# esp8266_minsys.net
KiCad netlist of a schematic drawn in EAGLE
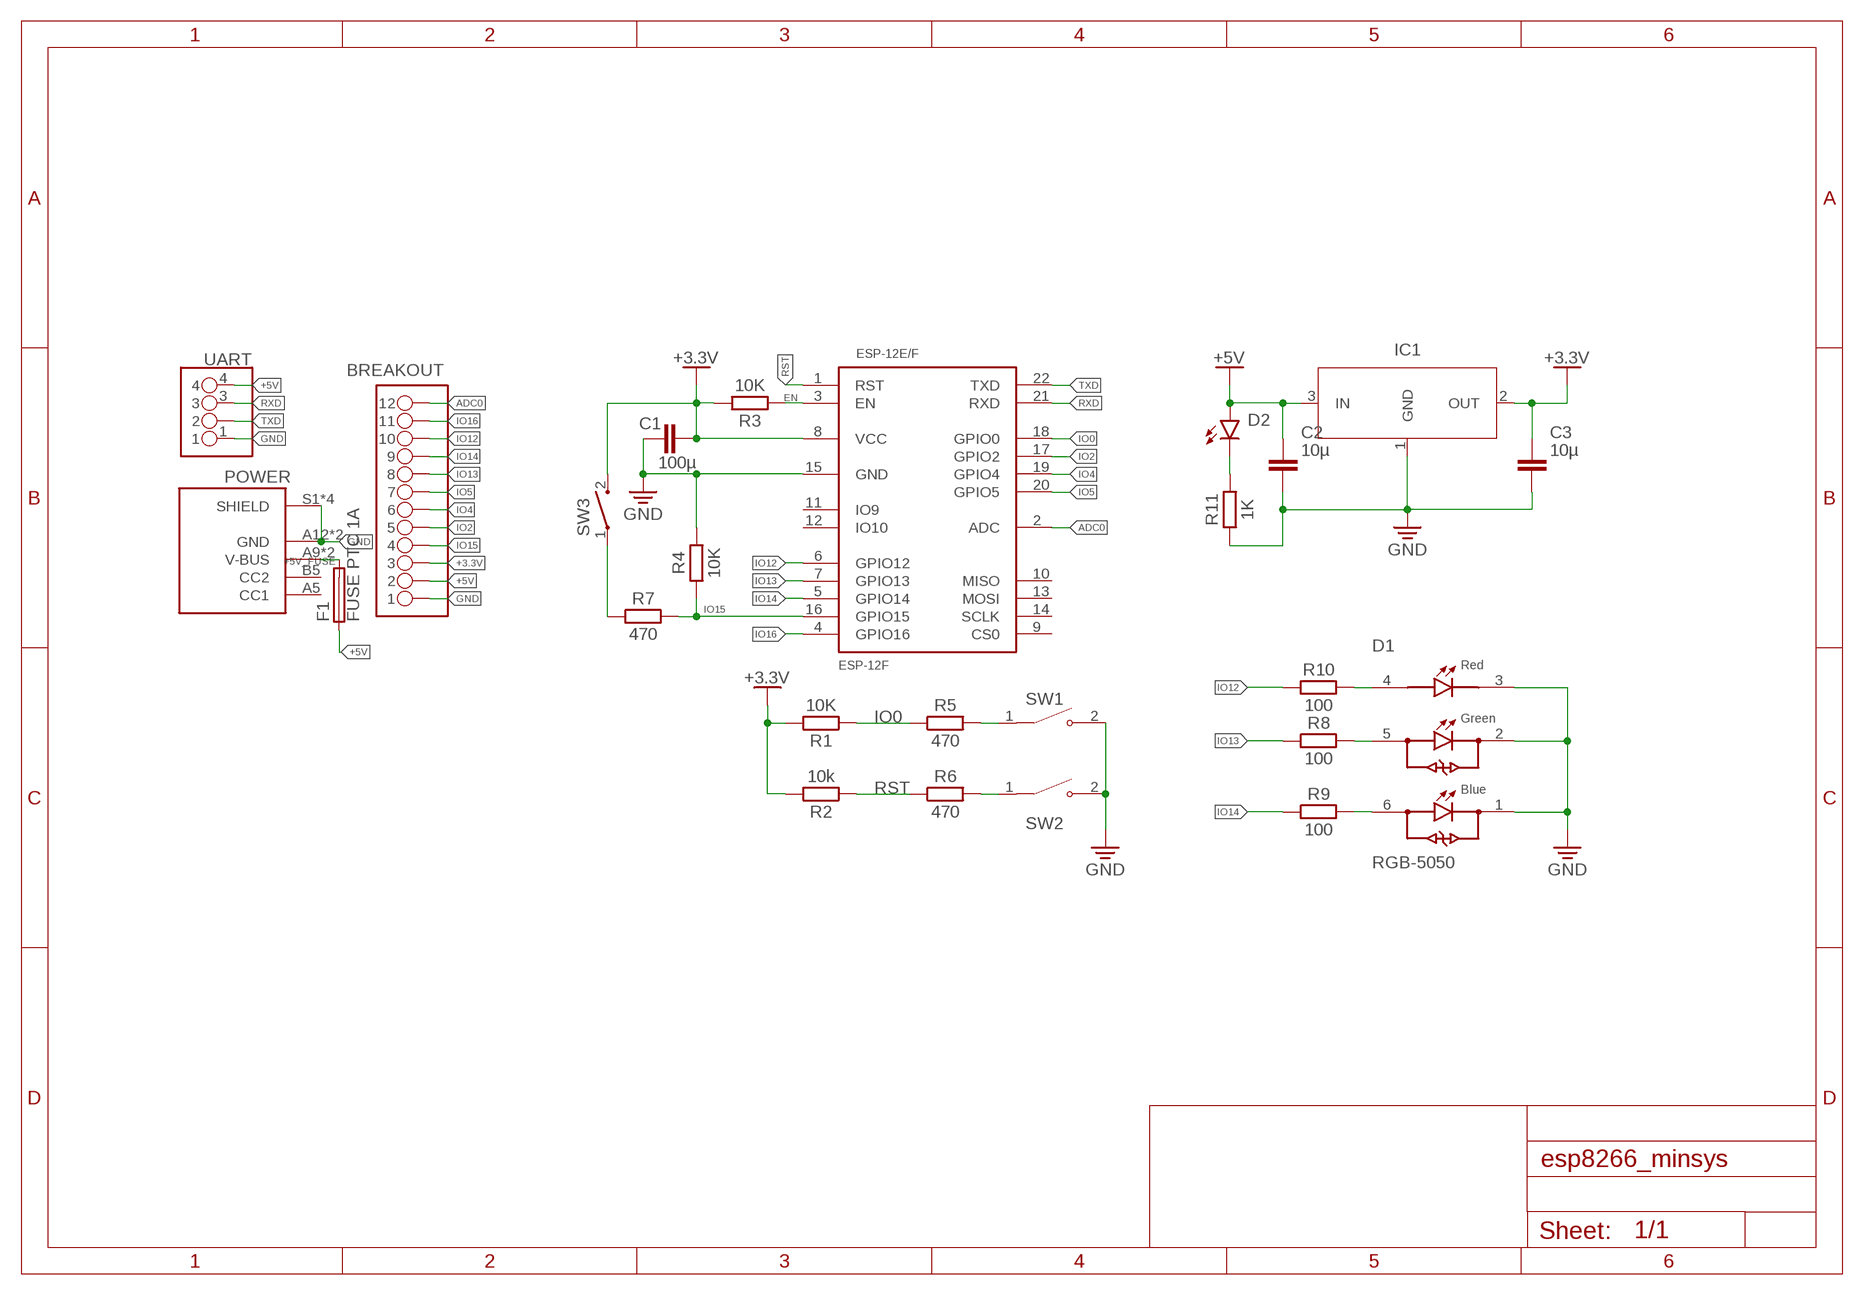
[diagram p0: schematic, sheet 1]

(export (version "E")
  (design (tool "Eeschema 10.0.6"))
  (components
    (comp (ref "BREAKOUT")
      (value "PINHD-1X12-BACKUP_1X12M")
      (footprint "eagle-import:1X12")
      (libsource (lib "eagle-import") (part "PINHD-1X12-BACKUP_1X12M"))
    )
    (comp (ref "C1")
      (value "100µ")
      (footprint "eagle-import:CAPM6032X280")
      (libsource (lib "eagle-import") (part "CTANTALUM-2412(6032-METRIC)_"))
    )
    (comp (ref "C2")
      (value "10µ")
      (footprint "eagle-import:CAPC2012X110")
      (libsource (lib "eagle-import") (part "CCHIP-0805(2012-METRIC)_"))
    )
    (comp (ref "C3")
      (value "10µ")
      (footprint "eagle-import:CAPC2012X110")
      (libsource (lib "eagle-import") (part "CCHIP-0805(2012-METRIC)_"))
    )
    (comp (ref "D1")
      (value "RGB-5050")
      (footprint "eagle-import:RGB-5050")
      (fields (field (name "MANUFACTURER") "Lite-On"))
      (libsource (lib "eagle-import") (part "RGB-5050"))
    )
    (comp (ref "D2")
      (value "LED_RED")
      (footprint "eagle-import:LEDC2012X110N_FLAT-R")
      (libsource (lib "eagle-import") (part "CHIP-FLAT-R_0805"))
    )
    (comp (ref "ESP-12E/F")
      (value "ESP-12F")
      (footprint "eagle-import:ESP-12F")
      (libsource (lib "eagle-import") (part "ESP-12F"))
    )
    (comp (ref "F1")
      (value "FUSE PTC 1A")
      (footprint "eagle-import:FUSC3215X82N")
      (libsource (lib "eagle-import") (part "FUSECHIP-1206(3216-METRIC)_"))
    )
    (comp (ref "IC1")
      (value "NCP1117ST33T3G")
      (footprint "eagle-import:SOT230P700X170-4")
      (fields (field (name "MANUFACTURER") "ON Semiconductor"))
      (libsource (lib "eagle-import") (part "NCP1117ST33T3GSOT-223"))
    )
    (comp (ref "POWER")
      (value "SOCKET-C")
      (footprint "eagle-import:SOCKET-C")
      (fields (field (name "MANUFACTURER") "CUI Devices"))
      (libsource (lib "eagle-import") (part "SOCKET-C"))
    )
    (comp (ref "R1")
      (value "10K")
      (footprint "eagle-import:RESC2012X65")
      (libsource (lib "eagle-import") (part "RCHIP-0805(2012-METRIC)_"))
    )
    (comp (ref "R2")
      (value "10k")
      (footprint "eagle-import:RESC2012X65")
      (libsource (lib "eagle-import") (part "RCHIP-0805(2012-METRIC)_"))
    )
    (comp (ref "R3")
      (value "10K")
      (footprint "eagle-import:RESC2012X65")
      (libsource (lib "eagle-import") (part "RCHIP-0805(2012-METRIC)_"))
    )
    (comp (ref "R4")
      (value "10K")
      (footprint "eagle-import:RESC2012X65")
      (libsource (lib "eagle-import") (part "RCHIP-0805(2012-METRIC)_"))
    )
    (comp (ref "R5")
      (value "470")
      (footprint "eagle-import:RESC2012X65")
      (libsource (lib "eagle-import") (part "RCHIP-0805(2012-METRIC)_"))
    )
    (comp (ref "R6")
      (value "470")
      (footprint "eagle-import:RESC2012X65")
      (libsource (lib "eagle-import") (part "RCHIP-0805(2012-METRIC)_"))
    )
    (comp (ref "R7")
      (value "470")
      (footprint "eagle-import:RESC2012X65")
      (libsource (lib "eagle-import") (part "RCHIP-0805(2012-METRIC)_"))
    )
    (comp (ref "R8")
      (value "100")
      (footprint "eagle-import:RESC2012X65")
      (libsource (lib "eagle-import") (part "RCHIP-0805(2012-METRIC)_"))
    )
    (comp (ref "R9")
      (value "100")
      (footprint "eagle-import:RESC2012X65")
      (libsource (lib "eagle-import") (part "RCHIP-0805(2012-METRIC)_"))
    )
    (comp (ref "R10")
      (value "100")
      (footprint "eagle-import:RESC2012X65")
      (libsource (lib "eagle-import") (part "RCHIP-0805(2012-METRIC)_"))
    )
    (comp (ref "R11")
      (value "1K")
      (footprint "eagle-import:RESC2012X65")
      (libsource (lib "eagle-import") (part "RCHIP-0805(2012-METRIC)_"))
    )
    (comp (ref "SW1")
      (value "SWITCH-2P")
      (footprint "eagle-import:SWITCH-2P")
      (fields (field (name "MANUFACTURER") "CUI Devices"))
      (libsource (lib "eagle-import") (part "SWITCH-2P"))
    )
    (comp (ref "SW2")
      (value "SWITCH-2P")
      (footprint "eagle-import:SWITCH-2P")
      (fields (field (name "MANUFACTURER") "CUI Devices"))
      (libsource (lib "eagle-import") (part "SWITCH-2P"))
    )
    (comp (ref "SW3")
      (value "SWITCH")
      (footprint "eagle-import:SW_1437566-3")
      (fields (field (name "MANUFACTURER") "TE CONNECTIVITY"))
      (libsource (lib "eagle-import") (part "SWITCH"))
    )
    (comp (ref "UART")
      (value "PINHD-1X04_1X04M")
      (footprint "eagle-import:1X04")
      (libsource (lib "eagle-import") (part "PINHD-1X04_1X04M"))
    )
  )
  (nets
    (net (code "1") (name "+3.3V") (class "Default")
      (node (ref "BREAKOUT") (pin "3") (pinfunction "3_3") (pintype "bidirectional"))
      (node (ref "C1") (pin "2") (pinfunction "2_2") (pintype "passive"))
      (node (ref "C3") (pin "1") (pinfunction "1_1") (pintype "passive"))
      (node (ref "ESP-12E/F") (pin "8") (pinfunction "VCC_8") (pintype "bidirectional"))
      (node (ref "IC1") (pin "2") (pinfunction "OUT_2") (pintype "output"))
      (node (ref "R1") (pin "2") (pinfunction "2_2") (pintype "passive"))
      (node (ref "R2") (pin "2") (pinfunction "2_2") (pintype "passive"))
      (node (ref "R3") (pin "2") (pinfunction "2_2") (pintype "passive"))
      (node (ref "SW3") (pin "2") (pinfunction "2_2") (pintype "passive"))
    )
    (net (code "2") (name "+5V") (class "Default")
      (node (ref "BREAKOUT") (pin "2") (pinfunction "2_2") (pintype "bidirectional"))
      (node (ref "C2") (pin "1") (pinfunction "1_1") (pintype "passive"))
      (node (ref "D2") (pin "A") (pinfunction "A_A") (pintype "passive"))
      (node (ref "F1") (pin "1") (pinfunction "1_1") (pintype "passive"))
      (node (ref "IC1") (pin "3") (pinfunction "IN_3") (pintype "input"))
      (node (ref "UART") (pin "4") (pinfunction "4_4") (pintype "bidirectional"))
    )
    (net (code "3") (name "/+5V_FUSE") (class "Default")
      (node (ref "F1") (pin "2") (pinfunction "2_2") (pintype "passive"))
      (node (ref "POWER") (pin "A9") (pinfunction "V-BUS_A9") (pintype "power_in"))
      (node (ref "POWER") (pin "B9") (pinfunction "V-BUS_B9") (pintype "power_in"))
    )
    (net (code "4") (name "/EN") (class "Default")
      (node (ref "ESP-12E/F") (pin "3") (pinfunction "EN_3") (pintype "bidirectional"))
      (node (ref "R3") (pin "1") (pinfunction "1_1") (pintype "passive"))
    )
    (net (code "5") (name "ADC0") (class "Default")
      (node (ref "BREAKOUT") (pin "12") (pinfunction "12_12") (pintype "bidirectional"))
      (node (ref "ESP-12E/F") (pin "2") (pinfunction "ADC_2") (pintype "bidirectional"))
    )
    (net (code "6") (name "GND") (class "Default")
      (node (ref "BREAKOUT") (pin "1") (pinfunction "1_1") (pintype "bidirectional"))
      (node (ref "C1") (pin "1") (pinfunction "1_1") (pintype "passive"))
      (node (ref "C2") (pin "2") (pinfunction "2_2") (pintype "passive"))
      (node (ref "C3") (pin "2") (pinfunction "2_2") (pintype "passive"))
      (node (ref "D1") (pin "1") (pinfunction "1_1") (pintype "passive"))
      (node (ref "D1") (pin "2") (pinfunction "2_2") (pintype "passive"))
      (node (ref "D1") (pin "3") (pinfunction "3_3") (pintype "passive"))
      (node (ref "ESP-12E/F") (pin "15") (pinfunction "GND_15") (pintype "bidirectional"))
      (node (ref "IC1") (pin "1") (pinfunction "GND_1") (pintype "passive"))
      (node (ref "POWER") (pin "A12") (pinfunction "GND_A12") (pintype "power_in"))
      (node (ref "POWER") (pin "B12") (pinfunction "GND_B12") (pintype "power_in"))
      (node (ref "POWER") (pin "S1") (pinfunction "SHIELD_S1") (pintype "passive"))
      (node (ref "POWER") (pin "S2") (pinfunction "SHIELD_S2") (pintype "passive"))
      (node (ref "POWER") (pin "S3") (pinfunction "SHIELD_S3") (pintype "passive"))
      (node (ref "POWER") (pin "S4") (pinfunction "SHIELD_S4") (pintype "passive"))
      (node (ref "R11") (pin "1") (pinfunction "1_1") (pintype "passive"))
      (node (ref "R4") (pin "2") (pinfunction "2_2") (pintype "passive"))
      (node (ref "SW1") (pin "2") (pinfunction "2_2") (pintype "passive"))
      (node (ref "SW2") (pin "2") (pinfunction "2_2") (pintype "passive"))
      (node (ref "UART") (pin "1") (pinfunction "1_1") (pintype "bidirectional"))
    )
    (net (code "7") (name "IO0") (class "Default")
      (node (ref "ESP-12E/F") (pin "18") (pinfunction "GPIO0_18") (pintype "bidirectional"))
      (node (ref "R1") (pin "1") (pinfunction "1_1") (pintype "passive"))
      (node (ref "R5") (pin "1") (pinfunction "1_1") (pintype "passive"))
    )
    (net (code "8") (name "IO2") (class "Default")
      (node (ref "BREAKOUT") (pin "5") (pinfunction "5_5") (pintype "bidirectional"))
      (node (ref "ESP-12E/F") (pin "17") (pinfunction "GPIO2_17") (pintype "bidirectional"))
    )
    (net (code "9") (name "IO4") (class "Default")
      (node (ref "BREAKOUT") (pin "6") (pinfunction "6_6") (pintype "bidirectional"))
      (node (ref "ESP-12E/F") (pin "19") (pinfunction "GPIO4_19") (pintype "bidirectional"))
    )
    (net (code "10") (name "IO5") (class "Default")
      (node (ref "BREAKOUT") (pin "7") (pinfunction "7_7") (pintype "bidirectional"))
      (node (ref "ESP-12E/F") (pin "20") (pinfunction "GPIO5_20") (pintype "bidirectional"))
    )
    (net (code "11") (name "IO12") (class "Default")
      (node (ref "BREAKOUT") (pin "10") (pinfunction "10_10") (pintype "bidirectional"))
      (node (ref "ESP-12E/F") (pin "6") (pinfunction "GPIO12_6") (pintype "bidirectional"))
      (node (ref "R10") (pin "1") (pinfunction "1_1") (pintype "passive"))
    )
    (net (code "12") (name "IO13") (class "Default")
      (node (ref "BREAKOUT") (pin "8") (pinfunction "8_8") (pintype "bidirectional"))
      (node (ref "ESP-12E/F") (pin "7") (pinfunction "GPIO13_7") (pintype "bidirectional"))
      (node (ref "R8") (pin "1") (pinfunction "1_1") (pintype "passive"))
    )
    (net (code "13") (name "IO14") (class "Default")
      (node (ref "BREAKOUT") (pin "9") (pinfunction "9_9") (pintype "bidirectional"))
      (node (ref "ESP-12E/F") (pin "5") (pinfunction "GPIO14_5") (pintype "bidirectional"))
      (node (ref "R9") (pin "1") (pinfunction "1_1") (pintype "passive"))
    )
    (net (code "14") (name "IO15") (class "Default")
      (node (ref "BREAKOUT") (pin "4") (pinfunction "4_4") (pintype "bidirectional"))
      (node (ref "ESP-12E/F") (pin "16") (pinfunction "GPIO15_16") (pintype "bidirectional"))
      (node (ref "R4") (pin "1") (pinfunction "1_1") (pintype "passive"))
      (node (ref "R7") (pin "2") (pinfunction "2_2") (pintype "passive"))
    )
    (net (code "15") (name "IO16") (class "Default")
      (node (ref "BREAKOUT") (pin "11") (pinfunction "11_11") (pintype "bidirectional"))
      (node (ref "ESP-12E/F") (pin "4") (pinfunction "GPIO16_4") (pintype "bidirectional"))
    )
    (net (code "16") (name "Net-(D1-Pad4)") (class "Default")
      (node (ref "D1") (pin "4") (pinfunction "4_4") (pintype "passive"))
      (node (ref "R10") (pin "2") (pinfunction "2_2") (pintype "passive"))
    )
    (net (code "17") (name "Net-(D1-Pad5)") (class "Default")
      (node (ref "D1") (pin "5") (pinfunction "5_5") (pintype "passive"))
      (node (ref "R8") (pin "2") (pinfunction "2_2") (pintype "passive"))
    )
    (net (code "18") (name "Net-(D1-Pad6)") (class "Default")
      (node (ref "D1") (pin "6") (pinfunction "6_6") (pintype "passive"))
      (node (ref "R9") (pin "2") (pinfunction "2_2") (pintype "passive"))
    )
    (net (code "19") (name "Net-(D2-PadC)") (class "Default")
      (node (ref "D2") (pin "C") (pinfunction "C_C") (pintype "passive"))
      (node (ref "R11") (pin "2") (pinfunction "2_2") (pintype "passive"))
    )
    (net (code "20") (name "Net-(R5-Pad2)") (class "Default")
      (node (ref "R5") (pin "2") (pinfunction "2_2") (pintype "passive"))
      (node (ref "SW1") (pin "1") (pinfunction "1_1") (pintype "passive"))
    )
    (net (code "21") (name "Net-(R6-Pad2)") (class "Default")
      (node (ref "R6") (pin "2") (pinfunction "2_2") (pintype "passive"))
      (node (ref "SW2") (pin "1") (pinfunction "1_1") (pintype "passive"))
    )
    (net (code "22") (name "Net-(R7-Pad1)") (class "Default")
      (node (ref "R7") (pin "1") (pinfunction "1_1") (pintype "passive"))
      (node (ref "SW3") (pin "1") (pinfunction "1_1") (pintype "passive"))
    )
    (net (code "23") (name "RST") (class "Default")
      (node (ref "ESP-12E/F") (pin "1") (pinfunction "RST_1") (pintype "bidirectional"))
      (node (ref "R2") (pin "1") (pinfunction "1_1") (pintype "passive"))
      (node (ref "R6") (pin "1") (pinfunction "1_1") (pintype "passive"))
    )
    (net (code "24") (name "RXD") (class "Default")
      (node (ref "ESP-12E/F") (pin "21") (pinfunction "RXD_21") (pintype "bidirectional"))
      (node (ref "UART") (pin "3") (pinfunction "3_3") (pintype "bidirectional"))
    )
    (net (code "25") (name "TXD") (class "Default")
      (node (ref "ESP-12E/F") (pin "22") (pinfunction "TXD_22") (pintype "bidirectional"))
      (node (ref "UART") (pin "2") (pinfunction "2_2") (pintype "bidirectional"))
    )
    (net (code "26") (name "unconnected-(ESP-12E/F-CS0-Pad9)") (class "Default")
      (node (ref "ESP-12E/F") (pin "9") (pinfunction "CS0_9") (pintype "bidirectional"))
    )
    (net (code "27") (name "unconnected-(ESP-12E/F-IO9-Pad11)") (class "Default")
      (node (ref "ESP-12E/F") (pin "11") (pinfunction "IO9_11") (pintype "bidirectional"))
    )
    (net (code "28") (name "unconnected-(ESP-12E/F-IO10-Pad12)") (class "Default")
      (node (ref "ESP-12E/F") (pin "12") (pinfunction "IO10_12") (pintype "bidirectional"))
    )
    (net (code "29") (name "unconnected-(ESP-12E/F-MISO-Pad10)") (class "Default")
      (node (ref "ESP-12E/F") (pin "10") (pinfunction "MISO_10") (pintype "bidirectional"))
    )
    (net (code "30") (name "unconnected-(ESP-12E/F-MOSI-Pad13)") (class "Default")
      (node (ref "ESP-12E/F") (pin "13") (pinfunction "MOSI_13") (pintype "bidirectional"))
    )
    (net (code "31") (name "unconnected-(ESP-12E/F-SCLK-Pad14)") (class "Default")
      (node (ref "ESP-12E/F") (pin "14") (pinfunction "SCLK_14") (pintype "bidirectional"))
    )
    (net (code "32") (name "unconnected-(POWER-CC1-PadA5)") (class "Default")
      (node (ref "POWER") (pin "A5") (pinfunction "CC1_A5") (pintype "bidirectional"))
    )
    (net (code "33") (name "unconnected-(POWER-CC2-PadB5)") (class "Default")
      (node (ref "POWER") (pin "B5") (pinfunction "CC2_B5") (pintype "bidirectional"))
    )
  )
)
